# HIH6130_Breakout.net
KiCad netlist of a schematic drawn in EAGLE
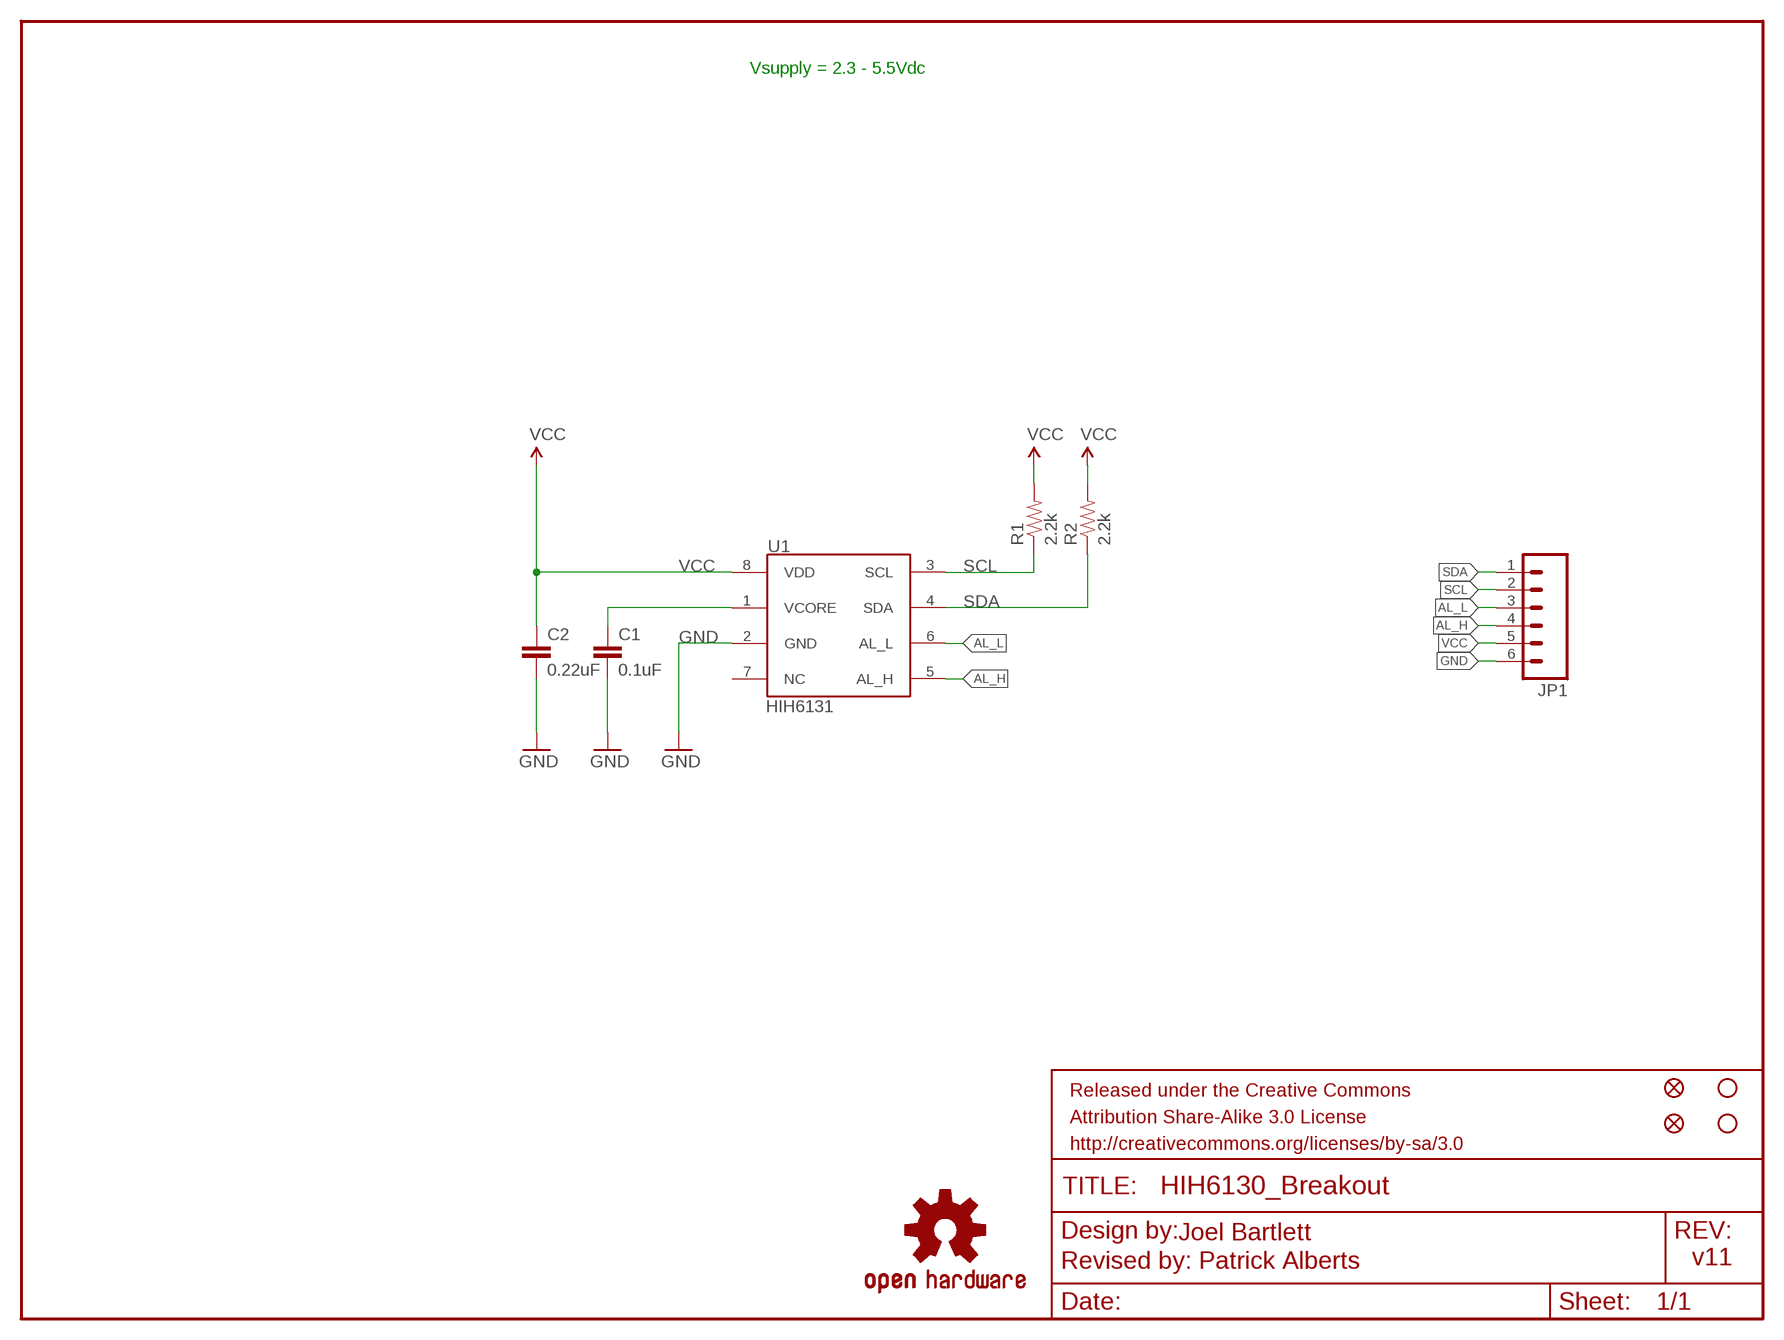
[diagram p0: schematic, sheet 1]

(export (version "E")
  (design (tool "Eeschema 10.0.6"))
  (components
    (comp (ref "C1")
      (value "0.1uF")
      (footprint "eagle-import:0603-CAP")
      (libsource (lib "eagle-import") (part "0.1UF-25V(+80/-20%)(0603)"))
    )
    (comp (ref "C2")
      (value "0.22uF")
      (footprint "eagle-import:0603-CAP")
      (libsource (lib "eagle-import") (part "0.22UF-25V-10%(0603)"))
    )
    (comp (ref "FID1")
      (value "FIDUCIAL1X2")
      (footprint "eagle-import:FIDUCIAL-1X2")
      (libsource (lib "eagle-import") (part "FIDUCIAL1X2"))
    )
    (comp (ref "FID2")
      (value "FIDUCIAL1X2")
      (footprint "eagle-import:FIDUCIAL-1X2")
      (libsource (lib "eagle-import") (part "FIDUCIAL1X2"))
    )
    (comp (ref "FRAME1")
      (value "FRAME-LETTER")
      (footprint "eagle-import:CREATIVE_COMMONS")
      (libsource (lib "eagle-import") (part "FRAME-LETTER"))
    )
    (comp (ref "JP1")
      (value "M06SIP")
      (footprint "eagle-import:1X06")
      (libsource (lib "eagle-import") (part "M06SIP"))
    )
    (comp (ref "JP3")
      (value "STAND-OFFTIGHT")
      (footprint "eagle-import:STAND-OFF-TIGHT")
      (libsource (lib "eagle-import") (part "STAND-OFFTIGHT"))
    )
    (comp (ref "JP4")
      (value "STAND-OFFTIGHT")
      (footprint "eagle-import:STAND-OFF-TIGHT")
      (libsource (lib "eagle-import") (part "STAND-OFFTIGHT"))
    )
    (comp (ref "R1")
      (value "2.2k")
      (footprint "eagle-import:0603-RES")
      (libsource (lib "eagle-import") (part "2.2KOHM1/10W1%(0603)"))
    )
    (comp (ref "R2")
      (value "2.2k")
      (footprint "eagle-import:0603-RES")
      (libsource (lib "eagle-import") (part "2.2KOHM1/10W1%(0603)"))
    )
    (comp (ref "U$2")
      (value "OSHW-LOGOS")
      (footprint "eagle-import:OSHW-LOGO-S")
      (libsource (lib "eagle-import") (part "OSHW-LOGOS"))
    )
    (comp (ref "U1")
      (value "HIH6131")
      (footprint "eagle-import:SOIC8")
      (libsource (lib "eagle-import") (part "HIH6131"))
    )
  )
  (nets
    (net (code "1") (name "AL_H") (class "Default")
      (node (ref "JP1") (pin "4") (pinfunction "4_4") (pintype "passive"))
      (node (ref "U1") (pin "5") (pinfunction "AL_H_5") (pintype "bidirectional"))
    )
    (net (code "2") (name "AL_L") (class "Default")
      (node (ref "JP1") (pin "3") (pinfunction "3_3") (pintype "passive"))
      (node (ref "U1") (pin "6") (pinfunction "AL_L_6") (pintype "bidirectional"))
    )
    (net (code "3") (name "GND") (class "Default")
      (node (ref "C1") (pin "2") (pinfunction "2_2") (pintype "passive"))
      (node (ref "C2") (pin "2") (pinfunction "2_2") (pintype "passive"))
      (node (ref "JP1") (pin "6") (pinfunction "6_6") (pintype "passive"))
      (node (ref "U1") (pin "2") (pinfunction "GND_2") (pintype "bidirectional"))
    )
    (net (code "4") (name "Net-(U1-VCORE)") (class "Default")
      (node (ref "C1") (pin "1") (pinfunction "1_1") (pintype "passive"))
      (node (ref "U1") (pin "1") (pinfunction "VCORE_1") (pintype "bidirectional"))
    )
    (net (code "5") (name "SCL") (class "Default")
      (node (ref "JP1") (pin "2") (pinfunction "2_2") (pintype "passive"))
      (node (ref "R1") (pin "1") (pinfunction "1_1") (pintype "passive"))
      (node (ref "U1") (pin "3") (pinfunction "SCL_3") (pintype "bidirectional"))
    )
    (net (code "6") (name "SDA") (class "Default")
      (node (ref "JP1") (pin "1") (pinfunction "1_1") (pintype "passive"))
      (node (ref "R2") (pin "1") (pinfunction "1_1") (pintype "passive"))
      (node (ref "U1") (pin "4") (pinfunction "SDA_4") (pintype "bidirectional"))
    )
    (net (code "7") (name "VCC") (class "Default")
      (node (ref "C2") (pin "1") (pinfunction "1_1") (pintype "passive"))
      (node (ref "JP1") (pin "5") (pinfunction "5_5") (pintype "passive"))
      (node (ref "R1") (pin "2") (pinfunction "2_2") (pintype "passive"))
      (node (ref "R2") (pin "2") (pinfunction "2_2") (pintype "passive"))
      (node (ref "U1") (pin "8") (pinfunction "VDD_8") (pintype "bidirectional"))
    )
    (net (code "8") (name "unconnected-(U1-NC-Pad7)") (class "Default")
      (node (ref "U1") (pin "7") (pinfunction "NC_7") (pintype "bidirectional"))
    )
  )
)
